# ecoshield.net
KiCad netlist of a schematic drawn in EAGLE
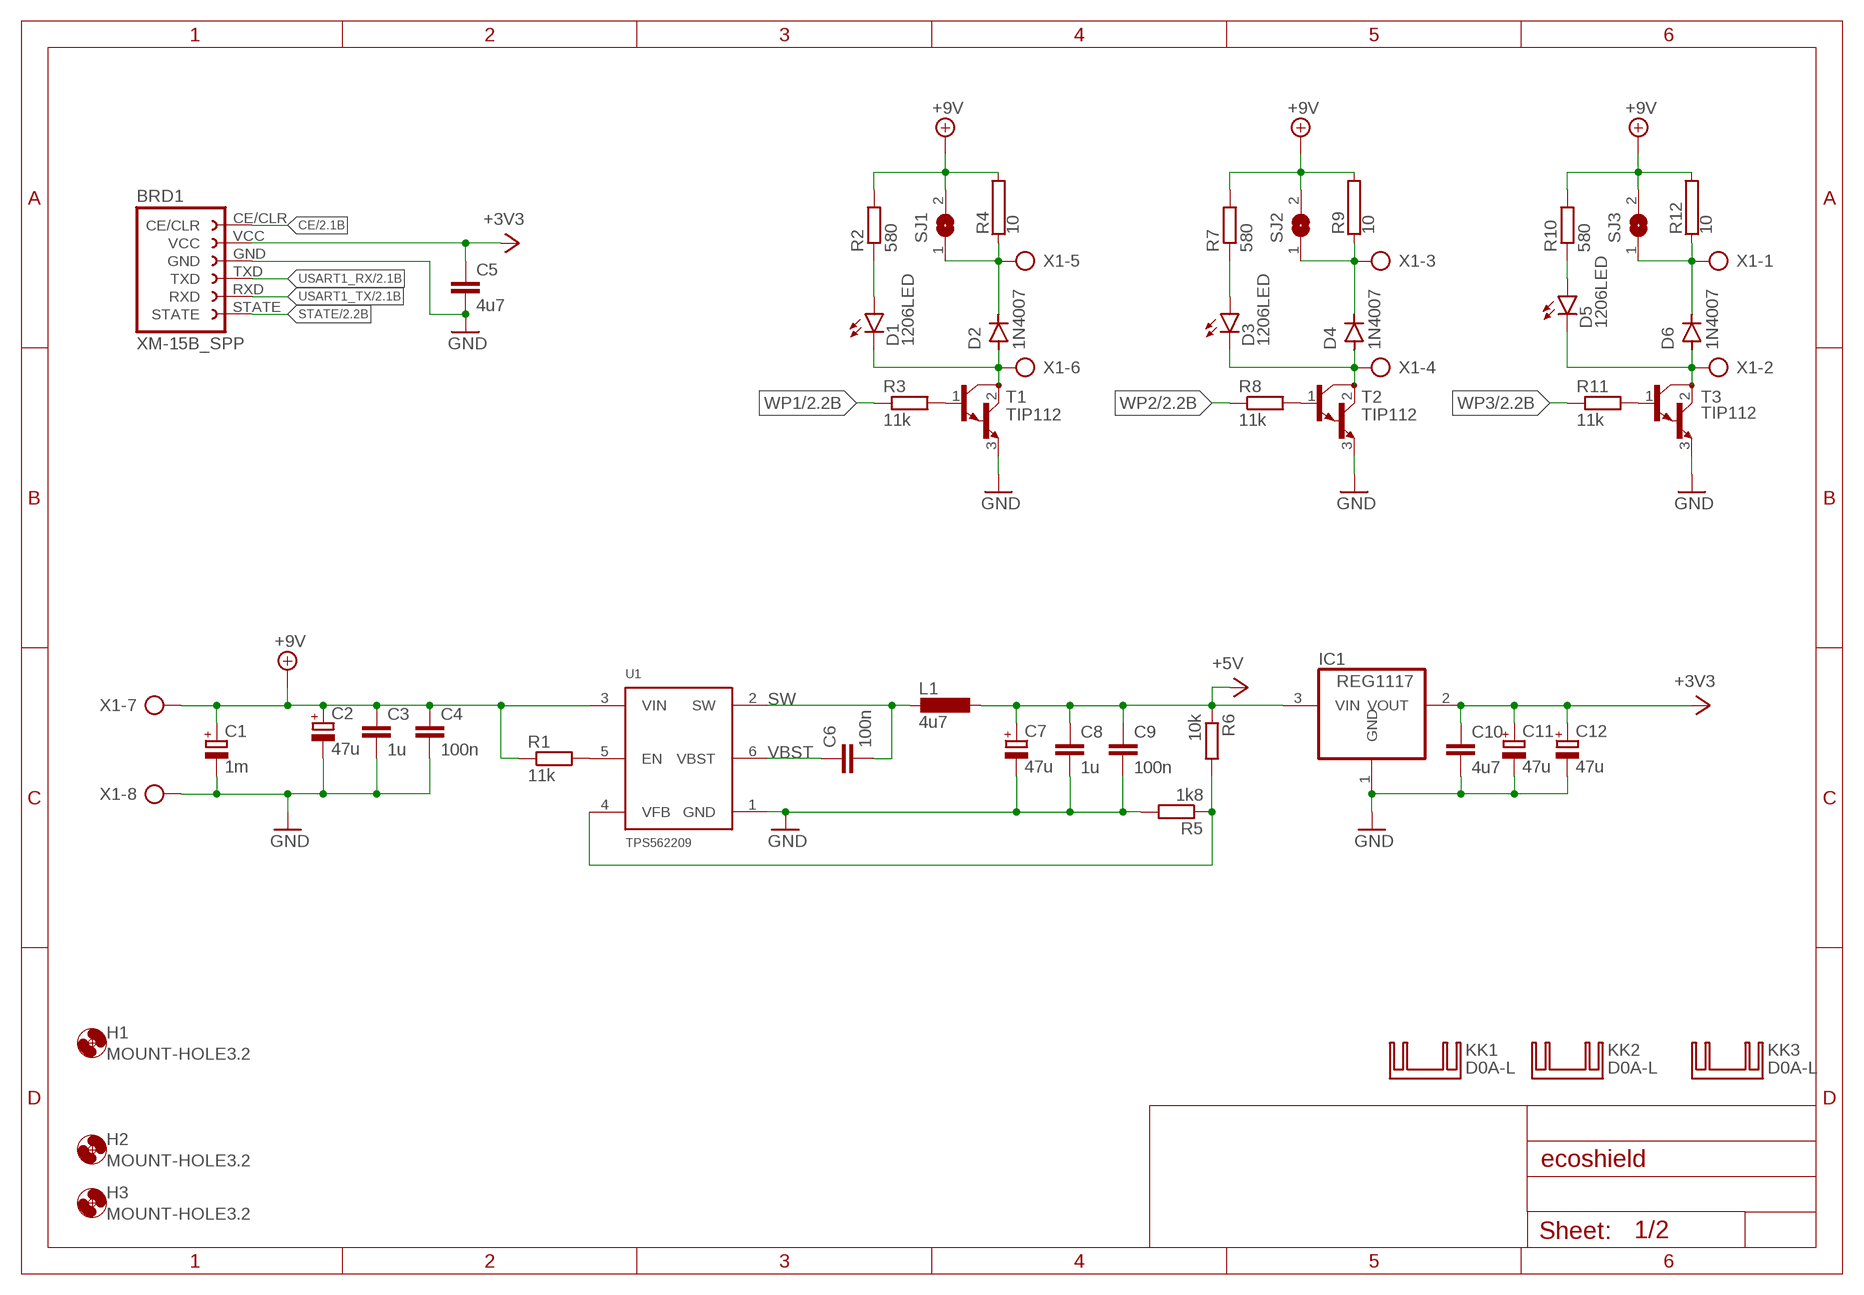
[diagram p0: schematic, sheet 1]
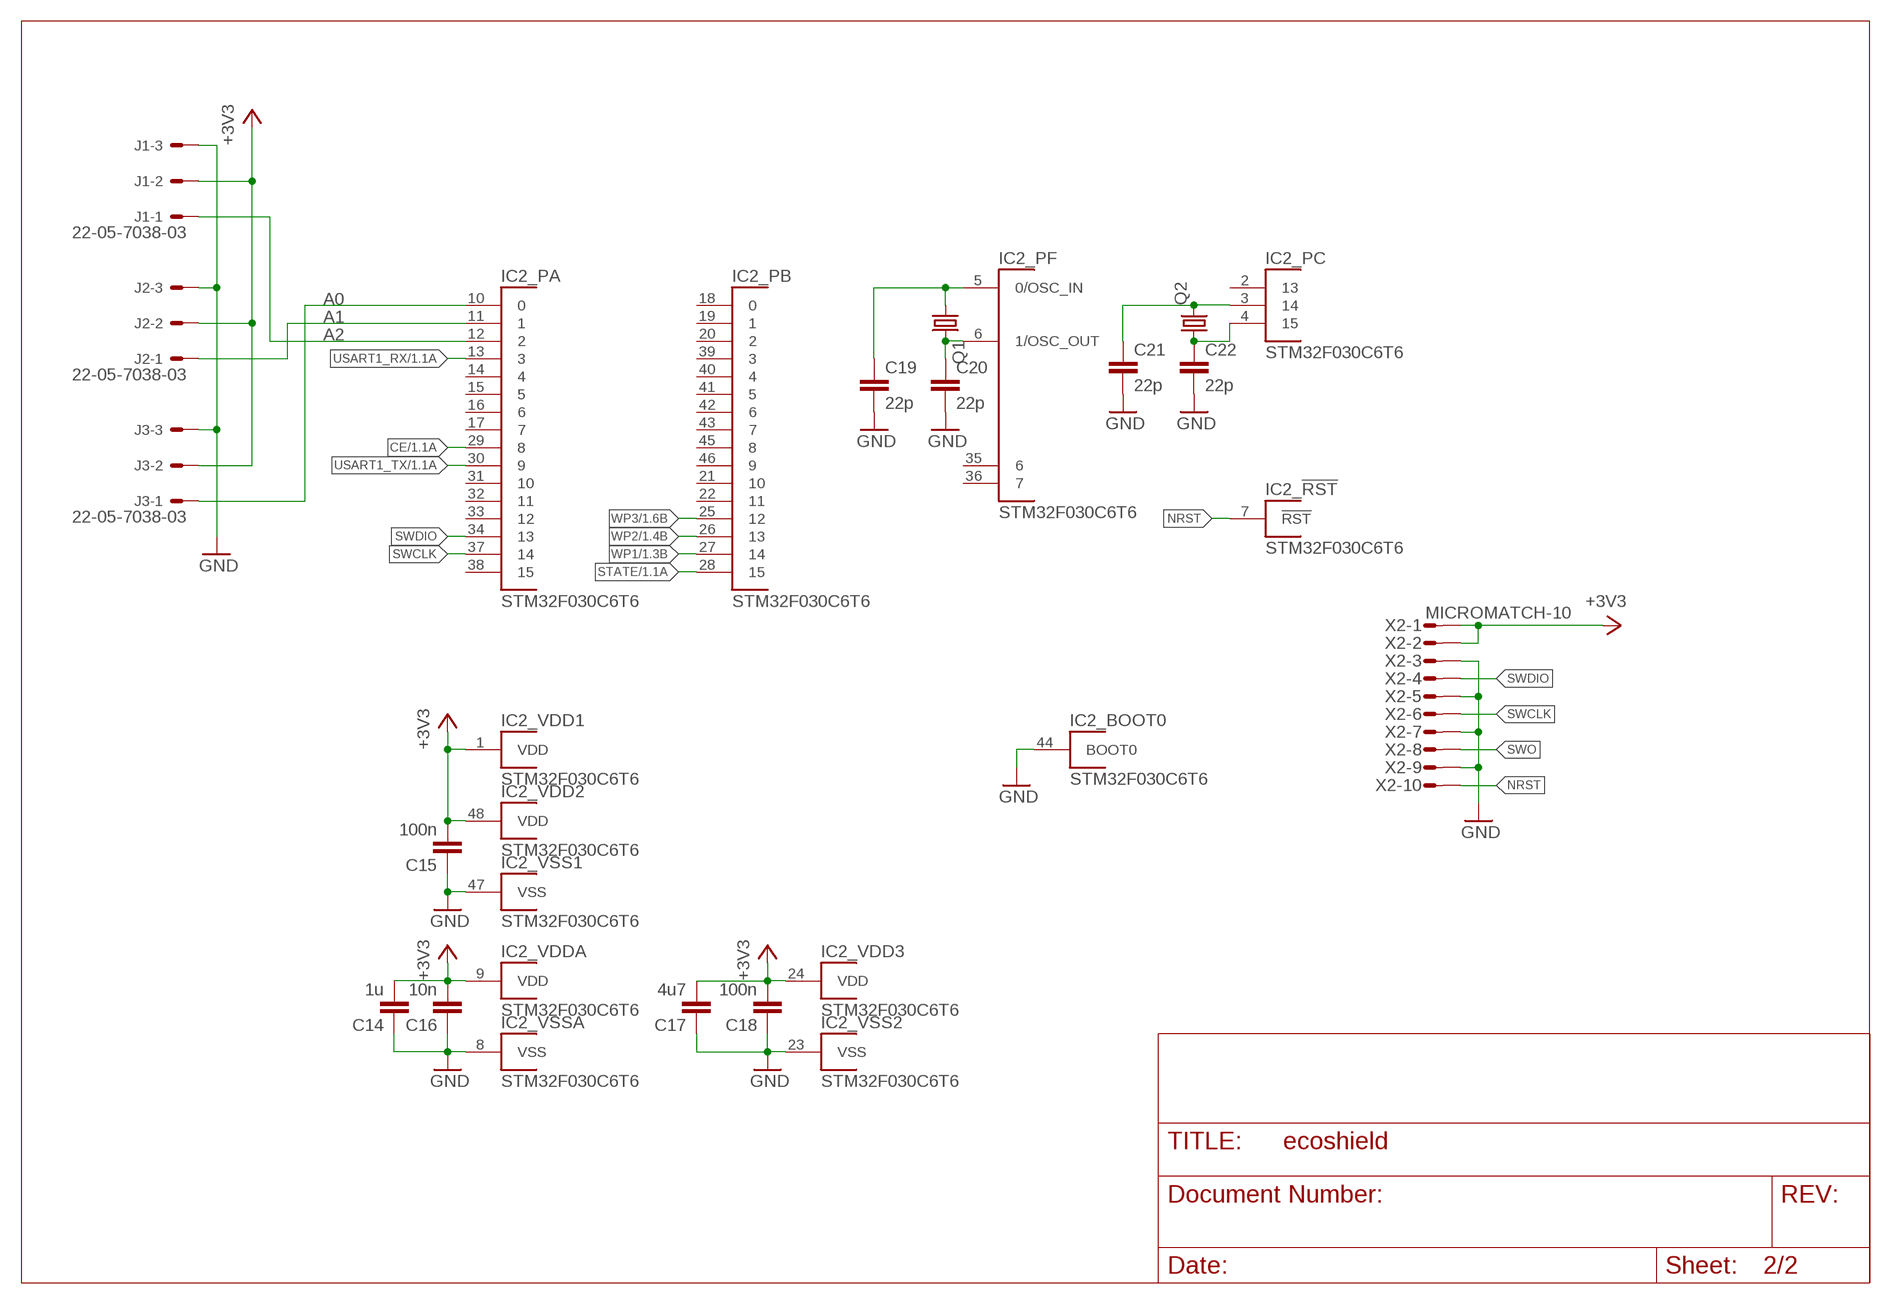
[diagram p1: schematic, sheet 2]

(export (version "E")
  (design (tool "Eeschema 10.0.6"))
  (components
    (comp (ref "C14")
      (value "1u")
      (footprint "eagle-import:C0805")
      (libsource (lib "eagle-import") (part "C-EUC0805"))
    )
    (comp (ref "C15")
      (value "100n")
      (footprint "eagle-import:C0805")
      (libsource (lib "eagle-import") (part "C-EUC0805"))
    )
    (comp (ref "C16")
      (value "10n")
      (footprint "eagle-import:C0805")
      (libsource (lib "eagle-import") (part "C-EUC0805"))
    )
    (comp (ref "C17")
      (value "4u7")
      (footprint "eagle-import:C0805")
      (libsource (lib "eagle-import") (part "C-EUC0805"))
    )
    (comp (ref "C18")
      (value "100n")
      (footprint "eagle-import:C0805")
      (libsource (lib "eagle-import") (part "C-EUC0805"))
    )
    (comp (ref "C19")
      (value "22p")
      (footprint "eagle-import:C0603")
      (libsource (lib "eagle-import") (part "C-EUC0603"))
    )
    (comp (ref "C20")
      (value "22p")
      (footprint "eagle-import:C0603")
      (libsource (lib "eagle-import") (part "C-EUC0603"))
    )
    (comp (ref "C21")
      (value "22p")
      (footprint "eagle-import:C0603")
      (libsource (lib "eagle-import") (part "C-EUC0603"))
    )
    (comp (ref "C22")
      (value "22p")
      (footprint "eagle-import:C0603")
      (libsource (lib "eagle-import") (part "C-EUC0603"))
    )
    (comp (ref "IC2")
      (value "STM32F030C6T6")
      (footprint "eagle-import:QFP50P900X900X160-48N")
      (libsource (lib "eagle-import") (part "STM32F030C6T6"))
    )
    (comp (ref "J1")
      (value "22-05-7038-03")
      (footprint "eagle-import:7395-03")
      (fields (field (name "MF") "MOLEX"))
      (libsource (lib "eagle-import") (part "22-?-0305-7038"))
    )
    (comp (ref "J2")
      (value "22-05-7038-03")
      (footprint "eagle-import:7395-03")
      (fields (field (name "MF") "MOLEX"))
      (libsource (lib "eagle-import") (part "22-?-0305-7038"))
    )
    (comp (ref "J3")
      (value "22-05-7038-03")
      (footprint "eagle-import:7395-03")
      (fields (field (name "MF") "MOLEX"))
      (libsource (lib "eagle-import") (part "22-?-0305-7038"))
    )
    (comp (ref "Q1")
      (value "CRYSTALHC49U-V")
      (footprint "eagle-import:HC49U-V")
      (libsource (lib "eagle-import") (part "CRYSTALHC49U-V"))
    )
    (comp (ref "Q2")
      (value "CRYSTALTC38H")
      (footprint "eagle-import:TC38H")
      (libsource (lib "eagle-import") (part "CRYSTALTC38H"))
    )
    (comp (ref "X2")
      (value "MICROMATCH-10")
      (footprint "eagle-import:MICROMATCH-10")
      (fields (field (name "MF") "FARNELL") (field (name "MPN") "8-215464-0"))
      (libsource (lib "eagle-import") (part "MICROMATCH-10"))
    )
    (comp (ref "BRD1")
      (value "XM-15B_SPP")
      (footprint "eagle-import:XM-15BSPP")
      (libsource (lib "eagle-import") (part "XM-15B_SPP"))
    )
    (comp (ref "C1")
      (value "1m")
      (footprint "eagle-import:E5-10,5")
      (libsource (lib "eagle-import") (part "CPOL-EUE5-10.5"))
    )
    (comp (ref "C2")
      (value "47u")
      (footprint "eagle-import:SMC_C")
      (libsource (lib "eagle-import") (part "CPOL-EUSMCC"))
    )
    (comp (ref "C3")
      (value "1u")
      (footprint "eagle-import:C0805")
      (libsource (lib "eagle-import") (part "C-EUC0805"))
    )
    (comp (ref "C4")
      (value "100n")
      (footprint "eagle-import:C0805")
      (libsource (lib "eagle-import") (part "C-EUC0805"))
    )
    (comp (ref "C5")
      (value "4u7")
      (footprint "eagle-import:C0805")
      (libsource (lib "eagle-import") (part "C-EUC0805"))
    )
    (comp (ref "C6")
      (value "100n")
      (footprint "eagle-import:C0805")
      (libsource (lib "eagle-import") (part "C-EUC0805"))
    )
    (comp (ref "C7")
      (value "47u")
      (footprint "eagle-import:SMC_C")
      (libsource (lib "eagle-import") (part "CPOL-EUSMCC"))
    )
    (comp (ref "C8")
      (value "1u")
      (footprint "eagle-import:C0805")
      (libsource (lib "eagle-import") (part "C-EUC0805"))
    )
    (comp (ref "C9")
      (value "100n")
      (footprint "eagle-import:C0805")
      (libsource (lib "eagle-import") (part "C-EUC0805"))
    )
    (comp (ref "C10")
      (value "4u7")
      (footprint "eagle-import:C0805")
      (libsource (lib "eagle-import") (part "C-EUC0805"))
    )
    (comp (ref "C11")
      (value "47u")
      (footprint "eagle-import:SMC_C")
      (libsource (lib "eagle-import") (part "CPOL-EUSMCC"))
    )
    (comp (ref "C12")
      (value "47u")
      (footprint "eagle-import:SMC_C")
      (libsource (lib "eagle-import") (part "CPOL-EUSMCC"))
    )
    (comp (ref "D1")
      (value "1206LED")
      (footprint "eagle-import:DIOC3216X70N")
      (libsource (lib "eagle-import") (part "1206LED"))
    )
    (comp (ref "D2")
      (value "1N4007")
      (footprint "eagle-import:DIOMELF4925N")
      (libsource (lib "eagle-import") (part "1N4007"))
    )
    (comp (ref "D3")
      (value "1206LED")
      (footprint "eagle-import:DIOC3216X70N")
      (libsource (lib "eagle-import") (part "1206LED"))
    )
    (comp (ref "D4")
      (value "1N4007")
      (footprint "eagle-import:DIOMELF4925N")
      (libsource (lib "eagle-import") (part "1N4007"))
    )
    (comp (ref "D5")
      (value "1206LED")
      (footprint "eagle-import:DIOC3216X70N")
      (libsource (lib "eagle-import") (part "1206LED"))
    )
    (comp (ref "D6")
      (value "1N4007")
      (footprint "eagle-import:DIOMELF4925N")
      (libsource (lib "eagle-import") (part "1N4007"))
    )
    (comp (ref "H1")
      (value "MOUNT-HOLE3.2")
      (footprint "eagle-import:3,2")
      (libsource (lib "eagle-import") (part "MOUNT-HOLE3.2"))
    )
    (comp (ref "H2")
      (value "MOUNT-HOLE3.2")
      (footprint "eagle-import:3,2")
      (libsource (lib "eagle-import") (part "MOUNT-HOLE3.2"))
    )
    (comp (ref "H3")
      (value "MOUNT-HOLE3.2")
      (footprint "eagle-import:3,2")
      (libsource (lib "eagle-import") (part "MOUNT-HOLE3.2"))
    )
    (comp (ref "IC1")
      (value "REG1117")
      (footprint "eagle-import:SOT223")
      (libsource (lib "eagle-import") (part "REG1117"))
    )
    (comp (ref "KK1")
      (value "D0A-L")
      (footprint "eagle-import:D02A-L")
      (libsource (lib "eagle-import") (part "D0A-L"))
    )
    (comp (ref "KK2")
      (value "D0A-L")
      (footprint "eagle-import:D02A-L")
      (libsource (lib "eagle-import") (part "D0A-L"))
    )
    (comp (ref "KK3")
      (value "D0A-L")
      (footprint "eagle-import:D02A-L")
      (libsource (lib "eagle-import") (part "D0A-L"))
    )
    (comp (ref "L1")
      (value "4u7")
      (footprint "eagle-import:744043004.")
      (libsource (lib "eagle-import") (part "744043004"))
    )
    (comp (ref "R1")
      (value "11k")
      (footprint "eagle-import:R1206")
      (libsource (lib "eagle-import") (part "R-EU_R1206"))
    )
    (comp (ref "R2")
      (value "580")
      (footprint "eagle-import:R1206")
      (libsource (lib "eagle-import") (part "R-EU_R1206"))
    )
    (comp (ref "R3")
      (value "11k")
      (footprint "eagle-import:R1206")
      (libsource (lib "eagle-import") (part "R-EU_R1206"))
    )
    (comp (ref "R4")
      (value "10")
      (footprint "eagle-import:AC05")
      (libsource (lib "eagle-import") (part "RAC05"))
    )
    (comp (ref "R5")
      (value "1k8")
      (footprint "eagle-import:R1206")
      (libsource (lib "eagle-import") (part "R-EU_R1206"))
    )
    (comp (ref "R6")
      (value "10k")
      (footprint "eagle-import:R1206")
      (libsource (lib "eagle-import") (part "R-EU_R1206"))
    )
    (comp (ref "R7")
      (value "580")
      (footprint "eagle-import:R1206")
      (libsource (lib "eagle-import") (part "R-EU_R1206"))
    )
    (comp (ref "R8")
      (value "11k")
      (footprint "eagle-import:R1206")
      (libsource (lib "eagle-import") (part "R-EU_R1206"))
    )
    (comp (ref "R9")
      (value "10")
      (footprint "eagle-import:AC05")
      (libsource (lib "eagle-import") (part "RAC05"))
    )
    (comp (ref "R10")
      (value "580")
      (footprint "eagle-import:R1206")
      (libsource (lib "eagle-import") (part "R-EU_R1206"))
    )
    (comp (ref "R11")
      (value "11k")
      (footprint "eagle-import:R1206")
      (libsource (lib "eagle-import") (part "R-EU_R1206"))
    )
    (comp (ref "R12")
      (value "10")
      (footprint "eagle-import:AC05")
      (libsource (lib "eagle-import") (part "RAC05"))
    )
    (comp (ref "SJ1")
      (value "SJW")
      (footprint "eagle-import:SJW")
      (libsource (lib "eagle-import") (part "SJW"))
    )
    (comp (ref "SJ2")
      (value "SJW")
      (footprint "eagle-import:SJW")
      (libsource (lib "eagle-import") (part "SJW"))
    )
    (comp (ref "SJ3")
      (value "SJW")
      (footprint "eagle-import:SJW")
      (libsource (lib "eagle-import") (part "SJW"))
    )
    (comp (ref "T1")
      (value "TIP112")
      (footprint "eagle-import:TO220")
      (libsource (lib "eagle-import") (part "TIP122"))
    )
    (comp (ref "T2")
      (value "TIP112")
      (footprint "eagle-import:TO220")
      (libsource (lib "eagle-import") (part "TIP122"))
    )
    (comp (ref "T3")
      (value "TIP112")
      (footprint "eagle-import:TO220")
      (libsource (lib "eagle-import") (part "TIP122"))
    )
    (comp (ref "U1")
      (value "TPS562209")
      (footprint "eagle-import:SOT95P280X110-6N")
      (libsource (lib "eagle-import") (part "TPS562209"))
    )
    (comp (ref "X1")
      (value "AK500/8")
      (footprint "eagle-import:AK500_8")
      (libsource (lib "eagle-import") (part "AK500/8"))
    )
  )
  (nets
    (net (code "1") (name "+3V3") (class "Default")
      (node (ref "BRD1") (pin "VCC") (pinfunction "VCC_VCC") (pintype "passive"))
      (node (ref "C10") (pin "1") (pinfunction "1_1") (pintype "passive"))
      (node (ref "C11") (pin "+") (pinfunction "+_+") (pintype "passive"))
      (node (ref "C12") (pin "+") (pinfunction "+_+") (pintype "passive"))
      (node (ref "C14") (pin "2") (pinfunction "2_2") (pintype "passive"))
      (node (ref "C15") (pin "2") (pinfunction "2_2") (pintype "passive"))
      (node (ref "C16") (pin "2") (pinfunction "2_2") (pintype "passive"))
      (node (ref "C17") (pin "2") (pinfunction "2_2") (pintype "passive"))
      (node (ref "C18") (pin "2") (pinfunction "2_2") (pintype "passive"))
      (node (ref "C5") (pin "1") (pinfunction "1_1") (pintype "passive"))
      (node (ref "IC1") (pin "2") (pinfunction "VOUT_2") (pintype "output"))
      (node (ref "IC2") (pin "1") (pinfunction "VDD_1") (pintype "bidirectional"))
      (node (ref "IC2") (pin "24") (pinfunction "VDD_24") (pintype "bidirectional"))
      (node (ref "IC2") (pin "48") (pinfunction "VDD_48") (pintype "bidirectional"))
      (node (ref "IC2") (pin "9") (pinfunction "VDD_9") (pintype "bidirectional"))
      (node (ref "J1") (pin "2") (pinfunction "S_2") (pintype "passive"))
      (node (ref "J2") (pin "2") (pinfunction "S_2") (pintype "passive"))
      (node (ref "J3") (pin "2") (pinfunction "S_2") (pintype "passive"))
      (node (ref "X2") (pin "1") (pinfunction "S_1") (pintype "passive"))
      (node (ref "X2") (pin "2") (pinfunction "S_2") (pintype "passive"))
    )
    (net (code "2") (name "+5V") (class "Default")
      (node (ref "C7") (pin "+") (pinfunction "+_+") (pintype "passive"))
      (node (ref "C8") (pin "1") (pinfunction "1_1") (pintype "passive"))
      (node (ref "C9") (pin "1") (pinfunction "1_1") (pintype "passive"))
      (node (ref "IC1") (pin "3") (pinfunction "VIN_3") (pintype "input"))
      (node (ref "L1") (pin "P$1") (pinfunction "1_P$1") (pintype "passive"))
      (node (ref "R6") (pin "1") (pinfunction "1_1") (pintype "passive"))
    )
    (net (code "3") (name "+9V") (class "Default")
      (node (ref "C1") (pin "+") (pinfunction "+_+") (pintype "passive"))
      (node (ref "C2") (pin "+") (pinfunction "+_+") (pintype "passive"))
      (node (ref "C3") (pin "1") (pinfunction "1_1") (pintype "passive"))
      (node (ref "C4") (pin "1") (pinfunction "1_1") (pintype "passive"))
      (node (ref "R1") (pin "1") (pinfunction "1_1") (pintype "passive"))
      (node (ref "R10") (pin "2") (pinfunction "2_2") (pintype "passive"))
      (node (ref "R12") (pin "2") (pinfunction "2_2") (pintype "passive"))
      (node (ref "R2") (pin "2") (pinfunction "2_2") (pintype "passive"))
      (node (ref "R4") (pin "2") (pinfunction "2_2") (pintype "passive"))
      (node (ref "R7") (pin "2") (pinfunction "2_2") (pintype "passive"))
      (node (ref "R9") (pin "2") (pinfunction "2_2") (pintype "passive"))
      (node (ref "SJ1") (pin "2") (pinfunction "2_2") (pintype "passive"))
      (node (ref "SJ2") (pin "2") (pinfunction "2_2") (pintype "passive"))
      (node (ref "SJ3") (pin "2") (pinfunction "2_2") (pintype "passive"))
      (node (ref "U1") (pin "3") (pinfunction "VIN_3") (pintype "power_in"))
      (node (ref "X1") (pin "7") (pinfunction "KL_7") (pintype "passive"))
    )
    (net (code "4") (name "A0") (class "Default")
      (node (ref "IC2") (pin "10") (pinfunction "0_10") (pintype "bidirectional"))
      (node (ref "J3") (pin "1") (pinfunction "S_1") (pintype "passive"))
    )
    (net (code "5") (name "A1") (class "Default")
      (node (ref "IC2") (pin "11") (pinfunction "1_11") (pintype "bidirectional"))
      (node (ref "J2") (pin "1") (pinfunction "S_1") (pintype "passive"))
    )
    (net (code "6") (name "A2") (class "Default")
      (node (ref "IC2") (pin "12") (pinfunction "2_12") (pintype "bidirectional"))
      (node (ref "J1") (pin "1") (pinfunction "S_1") (pintype "passive"))
    )
    (net (code "7") (name "CE") (class "Default")
      (node (ref "BRD1") (pin "CE/CLR") (pinfunction "CE/CLR_CE/CLR") (pintype "passive"))
      (node (ref "IC2") (pin "29") (pinfunction "8_29") (pintype "bidirectional"))
    )
    (net (code "8") (name "GND") (class "Default")
      (node (ref "BRD1") (pin "GND") (pinfunction "GND_GND") (pintype "passive"))
      (node (ref "C1") (pin "-") (pinfunction "-_-") (pintype "passive"))
      (node (ref "C10") (pin "2") (pinfunction "2_2") (pintype "passive"))
      (node (ref "C11") (pin "-") (pinfunction "-_-") (pintype "passive"))
      (node (ref "C12") (pin "-") (pinfunction "-_-") (pintype "passive"))
      (node (ref "C14") (pin "1") (pinfunction "1_1") (pintype "passive"))
      (node (ref "C15") (pin "1") (pinfunction "1_1") (pintype "passive"))
      (node (ref "C16") (pin "1") (pinfunction "1_1") (pintype "passive"))
      (node (ref "C17") (pin "1") (pinfunction "1_1") (pintype "passive"))
      (node (ref "C18") (pin "1") (pinfunction "1_1") (pintype "passive"))
      (node (ref "C19") (pin "2") (pinfunction "2_2") (pintype "passive"))
      (node (ref "C2") (pin "-") (pinfunction "-_-") (pintype "passive"))
      (node (ref "C20") (pin "2") (pinfunction "2_2") (pintype "passive"))
      (node (ref "C21") (pin "2") (pinfunction "2_2") (pintype "passive"))
      (node (ref "C22") (pin "2") (pinfunction "2_2") (pintype "passive"))
      (node (ref "C3") (pin "2") (pinfunction "2_2") (pintype "passive"))
      (node (ref "C4") (pin "2") (pinfunction "2_2") (pintype "passive"))
      (node (ref "C5") (pin "2") (pinfunction "2_2") (pintype "passive"))
      (node (ref "C7") (pin "-") (pinfunction "-_-") (pintype "passive"))
      (node (ref "C8") (pin "2") (pinfunction "2_2") (pintype "passive"))
      (node (ref "C9") (pin "2") (pinfunction "2_2") (pintype "passive"))
      (node (ref "IC1") (pin "1") (pinfunction "GND_1") (pintype "power_in"))
      (node (ref "IC2") (pin "23") (pinfunction "VSS_23") (pintype "bidirectional"))
      (node (ref "IC2") (pin "44") (pinfunction "BOOT0_44") (pintype "bidirectional"))
      (node (ref "IC2") (pin "47") (pinfunction "VSS_47") (pintype "bidirectional"))
      (node (ref "IC2") (pin "8") (pinfunction "VSS_8") (pintype "bidirectional"))
      (node (ref "J1") (pin "3") (pinfunction "S_3") (pintype "passive"))
      (node (ref "J2") (pin "3") (pinfunction "S_3") (pintype "passive"))
      (node (ref "J3") (pin "3") (pinfunction "S_3") (pintype "passive"))
      (node (ref "R5") (pin "2") (pinfunction "2_2") (pintype "passive"))
      (node (ref "T1") (pin "3") (pinfunction "E_3") (pintype "passive"))
      (node (ref "T2") (pin "3") (pinfunction "E_3") (pintype "passive"))
      (node (ref "T3") (pin "3") (pinfunction "E_3") (pintype "passive"))
      (node (ref "U1") (pin "1") (pinfunction "GND_1") (pintype "power_in"))
      (node (ref "X1") (pin "8") (pinfunction "KL_8") (pintype "passive"))
      (node (ref "X2") (pin "3") (pinfunction "S_3") (pintype "passive"))
      (node (ref "X2") (pin "5") (pinfunction "S_5") (pintype "passive"))
      (node (ref "X2") (pin "7") (pinfunction "S_7") (pintype "passive"))
      (node (ref "X2") (pin "9") (pinfunction "S_9") (pintype "passive"))
    )
    (net (code "9") (name "NRST") (class "Default")
      (node (ref "IC2") (pin "7") (pinfunction "~{RST}_7") (pintype "bidirectional"))
      (node (ref "X2") (pin "10") (pinfunction "S_10") (pintype "passive"))
    )
    (net (code "10") (name "Net-(D1-A)") (class "Default")
      (node (ref "D1") (pin "2") (pinfunction "A_2") (pintype "passive"))
      (node (ref "R2") (pin "1") (pinfunction "1_1") (pintype "passive"))
    )
    (net (code "11") (name "Net-(D1-C)") (class "Default")
      (node (ref "D1") (pin "1") (pinfunction "C_1") (pintype "passive"))
      (node (ref "D2") (pin "2") (pinfunction "A_2") (pintype "passive"))
      (node (ref "T1") (pin "2") (pinfunction "C_2") (pintype "passive"))
      (node (ref "X1") (pin "6") (pinfunction "KL_6") (pintype "passive"))
    )
    (net (code "12") (name "Net-(D2-C)") (class "Default")
      (node (ref "D2") (pin "1") (pinfunction "C_1") (pintype "passive"))
      (node (ref "R4") (pin "1") (pinfunction "1_1") (pintype "passive"))
      (node (ref "SJ1") (pin "1") (pinfunction "1_1") (pintype "passive"))
      (node (ref "X1") (pin "5") (pinfunction "KL_5") (pintype "passive"))
    )
    (net (code "13") (name "Net-(D3-A)") (class "Default")
      (node (ref "D3") (pin "2") (pinfunction "A_2") (pintype "passive"))
      (node (ref "R7") (pin "1") (pinfunction "1_1") (pintype "passive"))
    )
    (net (code "14") (name "Net-(D3-C)") (class "Default")
      (node (ref "D3") (pin "1") (pinfunction "C_1") (pintype "passive"))
      (node (ref "D4") (pin "2") (pinfunction "A_2") (pintype "passive"))
      (node (ref "T2") (pin "2") (pinfunction "C_2") (pintype "passive"))
      (node (ref "X1") (pin "4") (pinfunction "KL_4") (pintype "passive"))
    )
    (net (code "15") (name "Net-(D4-C)") (class "Default")
      (node (ref "D4") (pin "1") (pinfunction "C_1") (pintype "passive"))
      (node (ref "R9") (pin "1") (pinfunction "1_1") (pintype "passive"))
      (node (ref "SJ2") (pin "1") (pinfunction "1_1") (pintype "passive"))
      (node (ref "X1") (pin "3") (pinfunction "KL_3") (pintype "passive"))
    )
    (net (code "16") (name "Net-(D5-A)") (class "Default")
      (node (ref "D5") (pin "2") (pinfunction "A_2") (pintype "passive"))
      (node (ref "R10") (pin "1") (pinfunction "1_1") (pintype "passive"))
    )
    (net (code "17") (name "Net-(D5-C)") (class "Default")
      (node (ref "D5") (pin "1") (pinfunction "C_1") (pintype "passive"))
      (node (ref "D6") (pin "2") (pinfunction "A_2") (pintype "passive"))
      (node (ref "T3") (pin "2") (pinfunction "C_2") (pintype "passive"))
      (node (ref "X1") (pin "2") (pinfunction "KL_2") (pintype "passive"))
    )
    (net (code "18") (name "Net-(D6-C)") (class "Default")
      (node (ref "D6") (pin "1") (pinfunction "C_1") (pintype "passive"))
      (node (ref "R12") (pin "1") (pinfunction "1_1") (pintype "passive"))
      (node (ref "SJ3") (pin "1") (pinfunction "1_1") (pintype "passive"))
      (node (ref "X1") (pin "1") (pinfunction "KL_1") (pintype "passive"))
    )
    (net (code "19") (name "Net-(IC2E-14)") (class "Default")
      (node (ref "C21") (pin "1") (pinfunction "1_1") (pintype "passive"))
      (node (ref "IC2") (pin "3") (pinfunction "14_3") (pintype "bidirectional"))
      (node (ref "Q2") (pin "2") (pinfunction "2_2") (pintype "passive"))
    )
    (net (code "20") (name "Net-(IC2E-15)") (class "Default")
      (node (ref "C22") (pin "1") (pinfunction "1_1") (pintype "passive"))
      (node (ref "IC2") (pin "4") (pinfunction "15_4") (pintype "bidirectional"))
      (node (ref "Q2") (pin "1") (pinfunction "1_1") (pintype "passive"))
    )
    (net (code "21") (name "Net-(IC2F-0{slash}OSC_IN)") (class "Default")
      (node (ref "C19") (pin "1") (pinfunction "1_1") (pintype "passive"))
      (node (ref "IC2") (pin "5") (pinfunction "0/OSC_IN_5") (pintype "bidirectional"))
      (node (ref "Q1") (pin "1") (pinfunction "1_1") (pintype "passive"))
    )
    (net (code "22") (name "Net-(IC2F-1{slash}OSC_OUT)") (class "Default")
      (node (ref "C20") (pin "1") (pinfunction "1_1") (pintype "passive"))
      (node (ref "IC2") (pin "6") (pinfunction "1/OSC_OUT_6") (pintype "bidirectional"))
      (node (ref "Q1") (pin "2") (pinfunction "2_2") (pintype "passive"))
    )
    (net (code "23") (name "Net-(T1-B)") (class "Default")
      (node (ref "R3") (pin "2") (pinfunction "2_2") (pintype "passive"))
      (node (ref "T1") (pin "1") (pinfunction "B_1") (pintype "passive"))
    )
    (net (code "24") (name "Net-(T2-B)") (class "Default")
      (node (ref "R8") (pin "2") (pinfunction "2_2") (pintype "passive"))
      (node (ref "T2") (pin "1") (pinfunction "B_1") (pintype "passive"))
    )
    (net (code "25") (name "Net-(T3-B)") (class "Default")
      (node (ref "R11") (pin "2") (pinfunction "2_2") (pintype "passive"))
      (node (ref "T3") (pin "1") (pinfunction "B_1") (pintype "passive"))
    )
    (net (code "26") (name "Net-(U1-EN)") (class "Default")
      (node (ref "R1") (pin "2") (pinfunction "2_2") (pintype "passive"))
      (node (ref "U1") (pin "5") (pinfunction "EN_5") (pintype "input"))
    )
    (net (code "27") (name "Net-(U1-VFB)") (class "Default")
      (node (ref "R5") (pin "1") (pinfunction "1_1") (pintype "passive"))
      (node (ref "R6") (pin "2") (pinfunction "2_2") (pintype "passive"))
      (node (ref "U1") (pin "4") (pinfunction "VFB_4") (pintype "passive"))
    )
    (net (code "28") (name "STATE") (class "Default")
      (node (ref "BRD1") (pin "STATE") (pinfunction "STATE_STATE") (pintype "passive"))
      (node (ref "IC2") (pin "28") (pinfunction "15_28") (pintype "bidirectional"))
    )
    (net (code "29") (name "SW") (class "Default")
      (node (ref "C6") (pin "2") (pinfunction "2_2") (pintype "passive"))
      (node (ref "L1") (pin "P$2") (pinfunction "2_P$2") (pintype "passive"))
      (node (ref "U1") (pin "2") (pinfunction "SW_2") (pintype "power_in"))
    )
    (net (code "30") (name "SWCLK") (class "Default")
      (node (ref "IC2") (pin "37") (pinfunction "14_37") (pintype "bidirectional"))
      (node (ref "X2") (pin "6") (pinfunction "S_6") (pintype "passive"))
    )
    (net (code "31") (name "SWDIO") (class "Default")
      (node (ref "IC2") (pin "34") (pinfunction "13_34") (pintype "bidirectional"))
      (node (ref "X2") (pin "4") (pinfunction "S_4") (pintype "passive"))
    )
    (net (code "32") (name "SWO") (class "Default")
      (node (ref "X2") (pin "8") (pinfunction "S_8") (pintype "passive"))
    )
    (net (code "33") (name "USART1_RX") (class "Default")
      (node (ref "BRD1") (pin "TXD") (pinfunction "TXD_TXD") (pintype "passive"))
      (node (ref "IC2") (pin "13") (pinfunction "3_13") (pintype "bidirectional"))
    )
    (net (code "34") (name "USART1_TX") (class "Default")
      (node (ref "BRD1") (pin "RXD") (pinfunction "RXD_RXD") (pintype "passive"))
      (node (ref "IC2") (pin "30") (pinfunction "9_30") (pintype "bidirectional"))
    )
    (net (code "35") (name "VBST") (class "Default")
      (node (ref "C6") (pin "1") (pinfunction "1_1") (pintype "passive"))
      (node (ref "U1") (pin "6") (pinfunction "VBST_6") (pintype "passive"))
    )
    (net (code "36") (name "WP1") (class "Default")
      (node (ref "IC2") (pin "27") (pinfunction "14_27") (pintype "bidirectional"))
      (node (ref "R3") (pin "1") (pinfunction "1_1") (pintype "passive"))
    )
    (net (code "37") (name "WP2") (class "Default")
      (node (ref "IC2") (pin "26") (pinfunction "13_26") (pintype "bidirectional"))
      (node (ref "R8") (pin "1") (pinfunction "1_1") (pintype "passive"))
    )
    (net (code "38") (name "WP3") (class "Default")
      (node (ref "IC2") (pin "25") (pinfunction "12_25") (pintype "bidirectional"))
      (node (ref "R11") (pin "1") (pinfunction "1_1") (pintype "passive"))
    )
    (net (code "39") (name "unconnected-(IC2C-4-Pad14)") (class "Default")
      (node (ref "IC2") (pin "14") (pinfunction "4_14") (pintype "bidirectional"))
    )
    (net (code "40") (name "unconnected-(IC2C-5-Pad15)") (class "Default")
      (node (ref "IC2") (pin "15") (pinfunction "5_15") (pintype "bidirectional"))
    )
    (net (code "41") (name "unconnected-(IC2C-6-Pad16)") (class "Default")
      (node (ref "IC2") (pin "16") (pinfunction "6_16") (pintype "bidirectional"))
    )
    (net (code "42") (name "unconnected-(IC2C-7-Pad17)") (class "Default")
      (node (ref "IC2") (pin "17") (pinfunction "7_17") (pintype "bidirectional"))
    )
    (net (code "43") (name "unconnected-(IC2C-10-Pad31)") (class "Default")
      (node (ref "IC2") (pin "31") (pinfunction "10_31") (pintype "bidirectional"))
    )
    (net (code "44") (name "unconnected-(IC2C-11-Pad32)") (class "Default")
      (node (ref "IC2") (pin "32") (pinfunction "11_32") (pintype "bidirectional"))
    )
    (net (code "45") (name "unconnected-(IC2C-12-Pad33)") (class "Default")
      (node (ref "IC2") (pin "33") (pinfunction "12_33") (pintype "bidirectional"))
    )
    (net (code "46") (name "unconnected-(IC2C-15-Pad38)") (class "Default")
      (node (ref "IC2") (pin "38") (pinfunction "15_38") (pintype "bidirectional"))
    )
    (net (code "47") (name "unconnected-(IC2D-0-Pad18)") (class "Default")
      (node (ref "IC2") (pin "18") (pinfunction "0_18") (pintype "bidirectional"))
    )
    (net (code "48") (name "unconnected-(IC2D-1-Pad19)") (class "Default")
      (node (ref "IC2") (pin "19") (pinfunction "1_19") (pintype "bidirectional"))
    )
    (net (code "49") (name "unconnected-(IC2D-2-Pad20)") (class "Default")
      (node (ref "IC2") (pin "20") (pinfunction "2_20") (pintype "bidirectional"))
    )
    (net (code "50") (name "unconnected-(IC2D-3-Pad39)") (class "Default")
      (node (ref "IC2") (pin "39") (pinfunction "3_39") (pintype "bidirectional"))
    )
    (net (code "51") (name "unconnected-(IC2D-4-Pad40)") (class "Default")
      (node (ref "IC2") (pin "40") (pinfunction "4_40") (pintype "bidirectional"))
    )
    (net (code "52") (name "unconnected-(IC2D-5-Pad41)") (class "Default")
      (node (ref "IC2") (pin "41") (pinfunction "5_41") (pintype "bidirectional"))
    )
    (net (code "53") (name "unconnected-(IC2D-6-Pad42)") (class "Default")
      (node (ref "IC2") (pin "42") (pinfunction "6_42") (pintype "bidirectional"))
    )
    (net (code "54") (name "unconnected-(IC2D-7-Pad43)") (class "Default")
      (node (ref "IC2") (pin "43") (pinfunction "7_43") (pintype "bidirectional"))
    )
    (net (code "55") (name "unconnected-(IC2D-8-Pad45)") (class "Default")
      (node (ref "IC2") (pin "45") (pinfunction "8_45") (pintype "bidirectional"))
    )
    (net (code "56") (name "unconnected-(IC2D-9-Pad46)") (class "Default")
      (node (ref "IC2") (pin "46") (pinfunction "9_46") (pintype "bidirectional"))
    )
    (net (code "57") (name "unconnected-(IC2D-10-Pad21)") (class "Default")
      (node (ref "IC2") (pin "21") (pinfunction "10_21") (pintype "bidirectional"))
    )
    (net (code "58") (name "unconnected-(IC2D-11-Pad22)") (class "Default")
      (node (ref "IC2") (pin "22") (pinfunction "11_22") (pintype "bidirectional"))
    )
    (net (code "59") (name "unconnected-(IC2E-13-Pad2)") (class "Default")
      (node (ref "IC2") (pin "2") (pinfunction "13_2") (pintype "bidirectional"))
    )
    (net (code "60") (name "unconnected-(IC2F-6-Pad35)") (class "Default")
      (node (ref "IC2") (pin "35") (pinfunction "6_35") (pintype "bidirectional"))
    )
    (net (code "61") (name "unconnected-(IC2F-7-Pad36)") (class "Default")
      (node (ref "IC2") (pin "36") (pinfunction "7_36") (pintype "bidirectional"))
    )
  )
)
